# master_taylor2.net
KiCad netlist of a schematic drawn in EAGLE
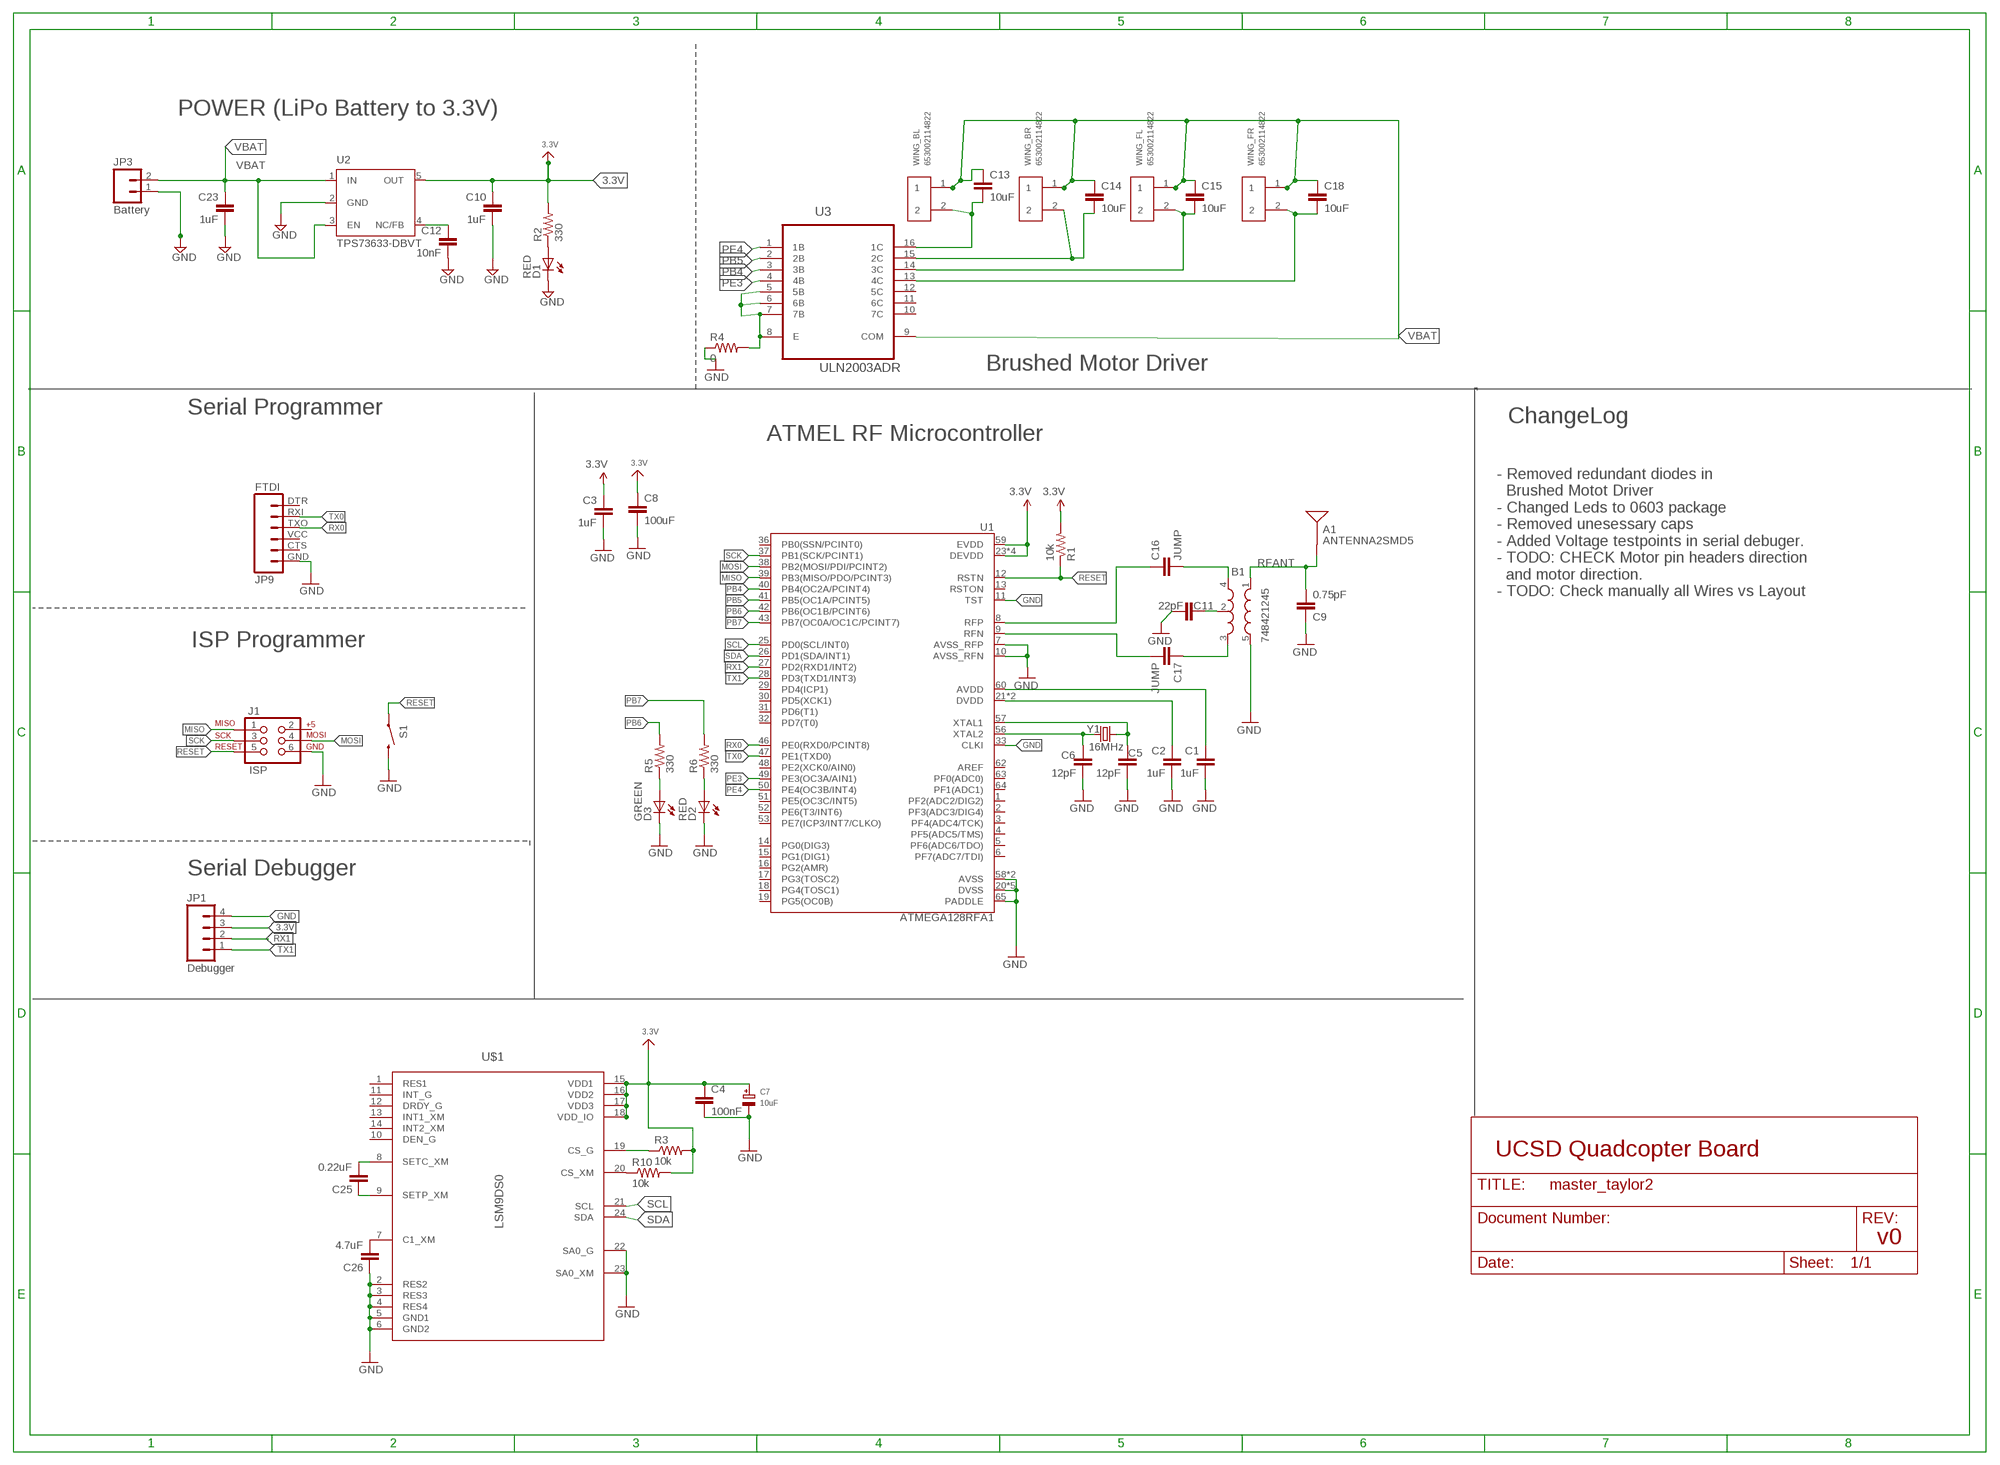
[diagram p0: schematic, sheet 1]

(export (version "E")
  (design (tool "Eeschema 10.0.6"))
  (components
    (comp (ref "A1")
      (value "ANTENNA2SMD5")
      (footprint "eagle-import:ANTENNA-CHIP5")
      (libsource (lib "eagle-import") (part "ANTENNA2SMD5"))
    )
    (comp (ref "B1")
      (value "748421245")
      (footprint "eagle-import:BALUN")
      (libsource (lib "eagle-import") (part "BALUN0805"))
    )
    (comp (ref "C1")
      (value "1uF")
      (footprint "eagle-import:0603-CAP")
      (libsource (lib "eagle-import") (part "CAP0603-CAP"))
    )
    (comp (ref "C2")
      (value "1uF")
      (footprint "eagle-import:0603-CAP")
      (libsource (lib "eagle-import") (part "CAP0603-CAP"))
    )
    (comp (ref "C3")
      (value "1uF")
      (footprint "eagle-import:0603-CAP")
      (libsource (lib "eagle-import") (part "CAP0603-CAP"))
    )
    (comp (ref "C4")
      (value "100nF")
      (footprint "eagle-import:0603-CAP")
      (libsource (lib "eagle-import") (part "CAP0603-CAP"))
    )
    (comp (ref "C5")
      (value "12pF")
      (footprint "eagle-import:0603-CAP")
      (libsource (lib "eagle-import") (part "CAP0603-CAP"))
    )
    (comp (ref "C6")
      (value "12pF")
      (footprint "eagle-import:0603-CAP")
      (libsource (lib "eagle-import") (part "CAP0603-CAP"))
    )
    (comp (ref "C7")
      (value "10uF")
      (footprint "eagle-import:EIA3216-18_A-W")
      (libsource (lib "eagle-import") (part "CAP_TANTALUMA/3216_WAVE"))
    )
    (comp (ref "C8")
      (value "100uF")
      (footprint "eagle-import:1206")
      (libsource (lib "eagle-import") (part "CAP1206"))
    )
    (comp (ref "C9")
      (value "0.75pF")
      (footprint "eagle-import:0603-CAP")
      (libsource (lib "eagle-import") (part "CAP0603-CAP"))
    )
    (comp (ref "C10")
      (value "1uF")
      (footprint "eagle-import:0603-CAP")
      (libsource (lib "eagle-import") (part "CAP0603-CAP"))
    )
    (comp (ref "C11")
      (value "22pF")
      (footprint "eagle-import:0603-CAP")
      (libsource (lib "eagle-import") (part "CAP0603-CAP"))
    )
    (comp (ref "C12")
      (value "10nF")
      (footprint "eagle-import:0603-CAP")
      (libsource (lib "eagle-import") (part "CAP0603-CAP"))
    )
    (comp (ref "C13")
      (value "10uF")
      (footprint "eagle-import:0603-CAP")
      (libsource (lib "eagle-import") (part "CAP0603-CAP"))
    )
    (comp (ref "C14")
      (value "10uF")
      (footprint "eagle-import:0603-CAP")
      (libsource (lib "eagle-import") (part "CAP0603-CAP"))
    )
    (comp (ref "C15")
      (value "10uF")
      (footprint "eagle-import:0603-CAP")
      (libsource (lib "eagle-import") (part "CAP0603-CAP"))
    )
    (comp (ref "C16")
      (value "JUMP")
      (footprint "eagle-import:0603-CAP")
      (libsource (lib "eagle-import") (part "CAP0603-CAP"))
    )
    (comp (ref "C17")
      (value "JUMP")
      (footprint "eagle-import:0603-CAP")
      (libsource (lib "eagle-import") (part "CAP0603-CAP"))
    )
    (comp (ref "C18")
      (value "10uF")
      (footprint "eagle-import:0603-CAP")
      (libsource (lib "eagle-import") (part "CAP0603-CAP"))
    )
    (comp (ref "C23")
      (value "1uF")
      (footprint "eagle-import:0603-CAP")
      (libsource (lib "eagle-import") (part "CAP0603-CAP"))
    )
    (comp (ref "C25")
      (value "0.22uF")
      (footprint "eagle-import:0603-CAP")
      (libsource (lib "eagle-import") (part "CAP0603-CAP"))
    )
    (comp (ref "C26")
      (value "4.7uF")
      (footprint "eagle-import:0603-CAP")
      (libsource (lib "eagle-import") (part "CAP0603-CAP"))
    )
    (comp (ref "D1")
      (value "RED")
      (footprint "eagle-import:CHIPLED_0603")
      (libsource (lib "eagle-import") (part "LEDCHIPLED_0603"))
    )
    (comp (ref "D2")
      (value "RED")
      (footprint "eagle-import:CHIPLED_0603")
      (libsource (lib "eagle-import") (part "LEDCHIPLED_0603"))
    )
    (comp (ref "D3")
      (value "GREEN")
      (footprint "eagle-import:CHIPLED_0603")
      (libsource (lib "eagle-import") (part "LEDCHIPLED_0603"))
    )
    (comp (ref "J1")
      (value "ISP")
      (footprint "eagle-import:2X3-NS")
      (libsource (lib "eagle-import") (part "AVR_SPI_PRG_6NS"))
    )
    (comp (ref "JP1")
      (value "Debugger")
      (footprint "eagle-import:1X04")
      (libsource (lib "eagle-import") (part "M04PTH"))
    )
    (comp (ref "JP3")
      (value "Battery")
      (footprint "eagle-import:1X02")
      (libsource (lib "eagle-import") (part "M02PTH"))
    )
    (comp (ref "JP9")
      (value "FTDI")
      (footprint "eagle-import:FTDI_BASIC")
      (libsource (lib "eagle-import") (part "FTDI_BASICPTH"))
    )
    (comp (ref "R1")
      (value "10k")
      (footprint "eagle-import:0603-RES")
      (libsource (lib "eagle-import") (part "SparkFun-Resistors_RESISTOR0603-RES"))
    )
    (comp (ref "R2")
      (value "330")
      (footprint "eagle-import:0603-RES")
      (libsource (lib "eagle-import") (part "SparkFun-Resistors_RESISTOR0603-RES"))
    )
    (comp (ref "R3")
      (value "10k")
      (footprint "eagle-import:0805")
      (libsource (lib "eagle-import") (part "RESISTOR0805-RES"))
    )
    (comp (ref "R4")
      (value "0")
      (footprint "eagle-import:0805")
      (libsource (lib "eagle-import") (part "RESISTOR0805-RES"))
    )
    (comp (ref "R5")
      (value "330")
      (footprint "eagle-import:0603-RES")
      (libsource (lib "eagle-import") (part "SparkFun-Resistors_RESISTOR0603-RES"))
    )
    (comp (ref "R6")
      (value "330")
      (footprint "eagle-import:0603-RES")
      (libsource (lib "eagle-import") (part "SparkFun-Resistors_RESISTOR0603-RES"))
    )
    (comp (ref "R10")
      (value "10k")
      (footprint "eagle-import:0805")
      (libsource (lib "eagle-import") (part "RESISTOR0805-RES"))
    )
    (comp (ref "S1")
      (value "SWITCH-MOMENTARY-2SMD")
      (footprint "eagle-import:TACTILE_SWITCH_SMD")
      (libsource (lib "eagle-import") (part "SWITCH-MOMENTARY-2SMD"))
    )
    (comp (ref "U$1")
      (value "LSM9DS0")
      (footprint "eagle-import:LGA-24")
      (libsource (lib "eagle-import") (part "LSM9DS0"))
    )
    (comp (ref "U1")
      (value "ATMEGA128RFA1")
      (footprint "eagle-import:QFN-64")
      (libsource (lib "eagle-import") (part "ATMEGA128RFA1"))
    )
    (comp (ref "U2")
      (value "TPS73633-DBVT")
      (footprint "eagle-import:SOT23-DBV")
      (libsource (lib "eagle-import") (part "TPS73633-DBVT"))
    )
    (comp (ref "U3")
      (value "ULN2003ADR")
      (footprint "eagle-import:SOIC127P600X175-16N")
      (libsource (lib "eagle-import") (part "ULN2003ADR"))
    )
    (comp (ref "WING_BL")
      (value "653002114822")
      (footprint "eagle-import:653002114822")
      (libsource (lib "eagle-import") (part "653002114822"))
    )
    (comp (ref "WING_BR")
      (value "653002114822")
      (footprint "eagle-import:653002114822")
      (libsource (lib "eagle-import") (part "653002114822"))
    )
    (comp (ref "WING_FL")
      (value "653002114822")
      (footprint "eagle-import:653002114822")
      (libsource (lib "eagle-import") (part "653002114822"))
    )
    (comp (ref "WING_FR")
      (value "653002114822")
      (footprint "eagle-import:653002114822")
      (libsource (lib "eagle-import") (part "653002114822"))
    )
    (comp (ref "Y1")
      (value "16MHz")
      (footprint "eagle-import:CRYSTAL-SMD-5X3")
      (libsource (lib "eagle-import") (part "CRYSTAL5X3"))
    )
  )
  (nets
    (net (code "1") (name "/RFANT") (class "Default")
      (node (ref "A1") (pin "FEED") (pinfunction "SIGNAL_FEED") (pintype "bidirectional"))
      (node (ref "B1") (pin "1") (pinfunction "IN_1") (pintype "bidirectional"))
      (node (ref "C9") (pin "2") (pinfunction "2_2") (pintype "passive"))
    )
    (net (code "2") (name "3.3V") (class "Default")
      (node (ref "C10") (pin "1") (pinfunction "1_1") (pintype "passive"))
      (node (ref "C3") (pin "1") (pinfunction "1_1") (pintype "passive"))
      (node (ref "C4") (pin "1") (pinfunction "1_1") (pintype "passive"))
      (node (ref "C7") (pin "+") (pinfunction "+_+") (pintype "passive"))
      (node (ref "C8") (pin "1") (pinfunction "1_1") (pintype "passive"))
      (node (ref "JP1") (pin "3") (pinfunction "3_3") (pintype "passive"))
      (node (ref "R1") (pin "2") (pinfunction "2_2") (pintype "passive"))
      (node (ref "R10") (pin "2") (pinfunction "2_2") (pintype "passive"))
      (node (ref "R2") (pin "2") (pinfunction "2_2") (pintype "passive"))
      (node (ref "R3") (pin "2") (pinfunction "2_2") (pintype "passive"))
      (node (ref "U$1") (pin "15") (pinfunction "VDD1_15") (pintype "bidirectional"))
      (node (ref "U$1") (pin "16") (pinfunction "VDD2_16") (pintype "bidirectional"))
      (node (ref "U$1") (pin "17") (pinfunction "VDD3_17") (pintype "bidirectional"))
      (node (ref "U$1") (pin "18") (pinfunction "VDD_IO_18") (pintype "bidirectional"))
      (node (ref "U1") (pin "23") (pinfunction "DEVDD_23") (pintype "bidirectional"))
      (node (ref "U1") (pin "34") (pinfunction "DEVDD_34") (pintype "bidirectional"))
      (node (ref "U1") (pin "44") (pinfunction "DEVDD_44") (pintype "bidirectional"))
      (node (ref "U1") (pin "54") (pinfunction "DEVDD_54") (pintype "bidirectional"))
      (node (ref "U1") (pin "59") (pinfunction "EVDD_59") (pintype "bidirectional"))
      (node (ref "U2") (pin "5") (pinfunction "OUT_5") (pintype "passive"))
    )
    (net (code "3") (name "GND") (class "Default")
      (node (ref "B1") (pin "5") (pinfunction "GND_5") (pintype "bidirectional"))
      (node (ref "C1") (pin "2") (pinfunction "2_2") (pintype "passive"))
      (node (ref "C10") (pin "2") (pinfunction "2_2") (pintype "passive"))
      (node (ref "C11") (pin "2") (pinfunction "2_2") (pintype "passive"))
      (node (ref "C12") (pin "2") (pinfunction "2_2") (pintype "passive"))
      (node (ref "C2") (pin "2") (pinfunction "2_2") (pintype "passive"))
      (node (ref "C23") (pin "2") (pinfunction "2_2") (pintype "passive"))
      (node (ref "C26") (pin "1") (pinfunction "1_1") (pintype "passive"))
      (node (ref "C3") (pin "2") (pinfunction "2_2") (pintype "passive"))
      (node (ref "C4") (pin "2") (pinfunction "2_2") (pintype "passive"))
      (node (ref "C5") (pin "2") (pinfunction "2_2") (pintype "passive"))
      (node (ref "C6") (pin "2") (pinfunction "2_2") (pintype "passive"))
      (node (ref "C7") (pin "-") (pinfunction "-_-") (pintype "passive"))
      (node (ref "C8") (pin "2") (pinfunction "2_2") (pintype "passive"))
      (node (ref "C9") (pin "1") (pinfunction "1_1") (pintype "passive"))
      (node (ref "D1") (pin "C") (pinfunction "C_C") (pintype "passive"))
      (node (ref "D2") (pin "C") (pinfunction "C_C") (pintype "passive"))
      (node (ref "D3") (pin "C") (pinfunction "C_C") (pintype "passive"))
      (node (ref "J1") (pin "6") (pinfunction "6_6") (pintype "passive"))
      (node (ref "JP1") (pin "4") (pinfunction "4_4") (pintype "passive"))
      (node (ref "JP3") (pin "1") (pinfunction "1_1") (pintype "passive"))
      (node (ref "JP9") (pin "GND") (pinfunction "6_GND") (pintype "passive"))
      (node (ref "R4") (pin "1") (pinfunction "1_1") (pintype "passive"))
      (node (ref "S1") (pin "3") (pinfunction "2_3") (pintype "passive"))
      (node (ref "U$1") (pin "2") (pinfunction "RES2_2") (pintype "bidirectional"))
      (node (ref "U$1") (pin "22") (pinfunction "SA0_G_22") (pintype "bidirectional"))
      (node (ref "U$1") (pin "23") (pinfunction "SA0_XM_23") (pintype "bidirectional"))
      (node (ref "U$1") (pin "3") (pinfunction "RES3_3") (pintype "bidirectional"))
      (node (ref "U$1") (pin "4") (pinfunction "RES4_4") (pintype "bidirectional"))
      (node (ref "U$1") (pin "5") (pinfunction "GND1_5") (pintype "bidirectional"))
      (node (ref "U$1") (pin "6") (pinfunction "GND2_6") (pintype "bidirectional"))
      (node (ref "U1") (pin "10") (pinfunction "AVSS_RFN_10") (pintype "bidirectional"))
      (node (ref "U1") (pin "11") (pinfunction "TST_11") (pintype "bidirectional"))
      (node (ref "U1") (pin "20") (pinfunction "DVSS_20") (pintype "bidirectional"))
      (node (ref "U1") (pin "24") (pinfunction "DVSS_24") (pintype "bidirectional"))
      (node (ref "U1") (pin "33") (pinfunction "CLKI_33") (pintype "bidirectional"))
      (node (ref "U1") (pin "35") (pinfunction "DVSS_35") (pintype "bidirectional"))
      (node (ref "U1") (pin "45") (pinfunction "DVSS_45") (pintype "bidirectional"))
      (node (ref "U1") (pin "55") (pinfunction "DVSS_55") (pintype "bidirectional"))
      (node (ref "U1") (pin "58") (pinfunction "AVSS_58") (pintype "bidirectional"))
      (node (ref "U1") (pin "61") (pinfunction "AVSS_61") (pintype "bidirectional"))
      (node (ref "U1") (pin "65") (pinfunction "PADDLE_65") (pintype "bidirectional"))
      (node (ref "U1") (pin "7") (pinfunction "AVSS_RFP_7") (pintype "bidirectional"))
      (node (ref "U2") (pin "2") (pinfunction "GND_2") (pintype "input"))
    )
    (net (code "4") (name "MISO") (class "Default")
      (node (ref "J1") (pin "1") (pinfunction "1_1") (pintype "passive"))
      (node (ref "U1") (pin "39") (pinfunction "PB3(MISO/PDO/PCINT3)_39") (pintype "bidirectional"))
    )
    (net (code "5") (name "MOSI") (class "Default")
      (node (ref "J1") (pin "4") (pinfunction "4_4") (pintype "passive"))
      (node (ref "U1") (pin "38") (pinfunction "PB2(MOSI/PDI/PCINT2)_38") (pintype "bidirectional"))
    )
    (net (code "6") (name "Net-(B1-GND-Pad2)") (class "Default")
      (node (ref "B1") (pin "2") (pinfunction "GND_2") (pintype "bidirectional"))
      (node (ref "C11") (pin "1") (pinfunction "1_1") (pintype "passive"))
    )
    (net (code "7") (name "Net-(B1-OUT1)") (class "Default")
      (node (ref "B1") (pin "4") (pinfunction "OUT1_4") (pintype "bidirectional"))
      (node (ref "C16") (pin "2") (pinfunction "2_2") (pintype "passive"))
    )
    (net (code "8") (name "Net-(B1-OUT2)") (class "Default")
      (node (ref "B1") (pin "3") (pinfunction "OUT2_3") (pintype "bidirectional"))
      (node (ref "C17") (pin "1") (pinfunction "1_1") (pintype "passive"))
    )
    (net (code "9") (name "Net-(C2-Pad1)") (class "Default")
      (node (ref "C2") (pin "1") (pinfunction "1_1") (pintype "passive"))
      (node (ref "U1") (pin "21") (pinfunction "DVDD_21") (pintype "bidirectional"))
      (node (ref "U1") (pin "22") (pinfunction "DVDD_22") (pintype "bidirectional"))
    )
    (net (code "10") (name "Net-(D1-PadA)") (class "Default")
      (node (ref "D1") (pin "A") (pinfunction "A_A") (pintype "passive"))
      (node (ref "R2") (pin "1") (pinfunction "1_1") (pintype "passive"))
    )
    (net (code "11") (name "Net-(D2-PadA)") (class "Default")
      (node (ref "D2") (pin "A") (pinfunction "A_A") (pintype "passive"))
      (node (ref "R6") (pin "1") (pinfunction "1_1") (pintype "passive"))
    )
    (net (code "12") (name "Net-(D3-PadA)") (class "Default")
      (node (ref "D3") (pin "A") (pinfunction "A_A") (pintype "passive"))
      (node (ref "R5") (pin "1") (pinfunction "1_1") (pintype "passive"))
    )
    (net (code "13") (name "Net-(U$1-C1_XM)") (class "Default")
      (node (ref "C26") (pin "2") (pinfunction "2_2") (pintype "passive"))
      (node (ref "U$1") (pin "7") (pinfunction "C1_XM_7") (pintype "bidirectional"))
    )
    (net (code "14") (name "Net-(U$1-CS_G)") (class "Default")
      (node (ref "R3") (pin "1") (pinfunction "1_1") (pintype "passive"))
      (node (ref "U$1") (pin "19") (pinfunction "CS_G_19") (pintype "bidirectional"))
    )
    (net (code "15") (name "Net-(U$1-CS_XM)") (class "Default")
      (node (ref "R10") (pin "1") (pinfunction "1_1") (pintype "passive"))
      (node (ref "U$1") (pin "20") (pinfunction "CS_XM_20") (pintype "bidirectional"))
    )
    (net (code "16") (name "Net-(U$1-SETC_XM)") (class "Default")
      (node (ref "C25") (pin "2") (pinfunction "2_2") (pintype "passive"))
      (node (ref "U$1") (pin "8") (pinfunction "SETC_XM_8") (pintype "bidirectional"))
    )
    (net (code "17") (name "Net-(U$1-SETP_XM)") (class "Default")
      (node (ref "C25") (pin "1") (pinfunction "1_1") (pintype "passive"))
      (node (ref "U$1") (pin "9") (pinfunction "SETP_XM_9") (pintype "bidirectional"))
    )
    (net (code "18") (name "Net-(U1-AVDD)") (class "Default")
      (node (ref "C1") (pin "1") (pinfunction "1_1") (pintype "passive"))
      (node (ref "U1") (pin "60") (pinfunction "AVDD_60") (pintype "bidirectional"))
    )
    (net (code "19") (name "Net-(U1-RFN)") (class "Default")
      (node (ref "C17") (pin "2") (pinfunction "2_2") (pintype "passive"))
      (node (ref "U1") (pin "9") (pinfunction "RFN_9") (pintype "bidirectional"))
    )
    (net (code "20") (name "Net-(U1-RFP)") (class "Default")
      (node (ref "C16") (pin "1") (pinfunction "1_1") (pintype "passive"))
      (node (ref "U1") (pin "8") (pinfunction "RFP_8") (pintype "bidirectional"))
    )
    (net (code "21") (name "Net-(U1-XTAL1)") (class "Default")
      (node (ref "C5") (pin "1") (pinfunction "1_1") (pintype "passive"))
      (node (ref "U1") (pin "57") (pinfunction "XTAL1_57") (pintype "bidirectional"))
      (node (ref "Y1") (pin "3") (pinfunction "2_3") (pintype "passive"))
    )
    (net (code "22") (name "Net-(U1-XTAL2)") (class "Default")
      (node (ref "C6") (pin "1") (pinfunction "1_1") (pintype "passive"))
      (node (ref "U1") (pin "56") (pinfunction "XTAL2_56") (pintype "bidirectional"))
      (node (ref "Y1") (pin "1") (pinfunction "1_1") (pintype "passive"))
    )
    (net (code "23") (name "Net-(U2-NC{slash}FB)") (class "Default")
      (node (ref "C12") (pin "1") (pinfunction "1_1") (pintype "passive"))
      (node (ref "U2") (pin "4") (pinfunction "NC/FB_4") (pintype "passive"))
    )
    (net (code "24") (name "Net-(U3-1C)") (class "Default")
      (node (ref "C13") (pin "2") (pinfunction "2_2") (pintype "passive"))
      (node (ref "U3") (pin "16") (pinfunction "1C_16") (pintype "output"))
      (node (ref "WING_BL") (pin "2") (pinfunction "2_2") (pintype "bidirectional"))
    )
    (net (code "25") (name "Net-(U3-2C)") (class "Default")
      (node (ref "C14") (pin "2") (pinfunction "2_2") (pintype "passive"))
      (node (ref "U3") (pin "15") (pinfunction "2C_15") (pintype "output"))
      (node (ref "WING_BR") (pin "2") (pinfunction "2_2") (pintype "bidirectional"))
    )
    (net (code "26") (name "Net-(U3-3C)") (class "Default")
      (node (ref "C15") (pin "2") (pinfunction "2_2") (pintype "passive"))
      (node (ref "U3") (pin "14") (pinfunction "3C_14") (pintype "output"))
      (node (ref "WING_FL") (pin "2") (pinfunction "2_2") (pintype "bidirectional"))
    )
    (net (code "27") (name "Net-(U3-4C)") (class "Default")
      (node (ref "C18") (pin "2") (pinfunction "2_2") (pintype "passive"))
      (node (ref "U3") (pin "13") (pinfunction "4C_13") (pintype "output"))
      (node (ref "WING_FR") (pin "2") (pinfunction "2_2") (pintype "bidirectional"))
    )
    (net (code "28") (name "Net-(U3-5B)") (class "Default")
      (node (ref "R4") (pin "2") (pinfunction "2_2") (pintype "passive"))
      (node (ref "U3") (pin "5") (pinfunction "5B_5") (pintype "input"))
      (node (ref "U3") (pin "6") (pinfunction "6B_6") (pintype "input"))
      (node (ref "U3") (pin "7") (pinfunction "7B_7") (pintype "input"))
      (node (ref "U3") (pin "8") (pinfunction "E_8") (pintype "input"))
    )
    (net (code "29") (name "PB4") (class "Default")
      (node (ref "U1") (pin "40") (pinfunction "PB4(OC2A/PCINT4)_40") (pintype "bidirectional"))
      (node (ref "U3") (pin "3") (pinfunction "3B_3") (pintype "input"))
    )
    (net (code "30") (name "PB5") (class "Default")
      (node (ref "U1") (pin "41") (pinfunction "PB5(OC1A/PCINT5)_41") (pintype "bidirectional"))
      (node (ref "U3") (pin "2") (pinfunction "2B_2") (pintype "input"))
    )
    (net (code "31") (name "PB6") (class "Default")
      (node (ref "R5") (pin "2") (pinfunction "2_2") (pintype "passive"))
      (node (ref "U1") (pin "42") (pinfunction "PB6(OC1B/PCINT6)_42") (pintype "bidirectional"))
    )
    (net (code "32") (name "PB7") (class "Default")
      (node (ref "R6") (pin "2") (pinfunction "2_2") (pintype "passive"))
      (node (ref "U1") (pin "43") (pinfunction "PB7(OC0A/OC1C/PCINT7)_43") (pintype "bidirectional"))
    )
    (net (code "33") (name "PE3") (class "Default")
      (node (ref "U1") (pin "49") (pinfunction "PE3(OC3A/AIN1)_49") (pintype "bidirectional"))
      (node (ref "U3") (pin "4") (pinfunction "4B_4") (pintype "input"))
    )
    (net (code "34") (name "PE4") (class "Default")
      (node (ref "U1") (pin "50") (pinfunction "PE4(OC3B/INT4)_50") (pintype "bidirectional"))
      (node (ref "U3") (pin "1") (pinfunction "1B_1") (pintype "input"))
    )
    (net (code "35") (name "RESET") (class "Default")
      (node (ref "J1") (pin "5") (pinfunction "5_5") (pintype "passive"))
      (node (ref "R1") (pin "1") (pinfunction "1_1") (pintype "passive"))
      (node (ref "S1") (pin "1") (pinfunction "1_1") (pintype "passive"))
      (node (ref "U1") (pin "12") (pinfunction "RSTN_12") (pintype "bidirectional"))
    )
    (net (code "36") (name "RX0") (class "Default")
      (node (ref "JP9") (pin "TXO") (pinfunction "3_TXO") (pintype "passive"))
      (node (ref "U1") (pin "46") (pinfunction "PE0(RXD0/PCINT8)_46") (pintype "bidirectional"))
    )
    (net (code "37") (name "RX1") (class "Default")
      (node (ref "JP1") (pin "2") (pinfunction "2_2") (pintype "passive"))
      (node (ref "U1") (pin "27") (pinfunction "PD2(RXD1/INT2)_27") (pintype "bidirectional"))
    )
    (net (code "38") (name "SCK") (class "Default")
      (node (ref "J1") (pin "3") (pinfunction "3_3") (pintype "passive"))
      (node (ref "U1") (pin "37") (pinfunction "PB1(SCK/PCINT1)_37") (pintype "bidirectional"))
    )
    (net (code "39") (name "SCL") (class "Default")
      (node (ref "U$1") (pin "21") (pinfunction "SCL_21") (pintype "bidirectional"))
      (node (ref "U1") (pin "25") (pinfunction "PD0(SCL/INT0)_25") (pintype "bidirectional"))
    )
    (net (code "40") (name "SDA") (class "Default")
      (node (ref "U$1") (pin "24") (pinfunction "SDA_24") (pintype "bidirectional"))
      (node (ref "U1") (pin "26") (pinfunction "PD1(SDA/INT1)_26") (pintype "bidirectional"))
    )
    (net (code "41") (name "TX0") (class "Default")
      (node (ref "JP9") (pin "RXI") (pinfunction "2_RXI") (pintype "passive"))
      (node (ref "U1") (pin "47") (pinfunction "PE1(TXD0)_47") (pintype "bidirectional"))
    )
    (net (code "42") (name "TX1") (class "Default")
      (node (ref "JP1") (pin "1") (pinfunction "1_1") (pintype "passive"))
      (node (ref "U1") (pin "28") (pinfunction "PD3(TXD1/INT3)_28") (pintype "bidirectional"))
    )
    (net (code "43") (name "VBAT") (class "Default")
      (node (ref "C13") (pin "1") (pinfunction "1_1") (pintype "passive"))
      (node (ref "C14") (pin "1") (pinfunction "1_1") (pintype "passive"))
      (node (ref "C15") (pin "1") (pinfunction "1_1") (pintype "passive"))
      (node (ref "C18") (pin "1") (pinfunction "1_1") (pintype "passive"))
      (node (ref "C23") (pin "1") (pinfunction "1_1") (pintype "passive"))
      (node (ref "JP3") (pin "2") (pinfunction "2_2") (pintype "passive"))
      (node (ref "U2") (pin "1") (pinfunction "IN_1") (pintype "input"))
      (node (ref "U2") (pin "3") (pinfunction "EN_3") (pintype "power_in"))
      (node (ref "U3") (pin "9") (pinfunction "COM_9") (pintype "output"))
      (node (ref "WING_BL") (pin "1") (pinfunction "1_1") (pintype "bidirectional"))
      (node (ref "WING_BR") (pin "1") (pinfunction "1_1") (pintype "bidirectional"))
      (node (ref "WING_FL") (pin "1") (pinfunction "1_1") (pintype "bidirectional"))
      (node (ref "WING_FR") (pin "1") (pinfunction "1_1") (pintype "bidirectional"))
    )
    (net (code "44") (name "unconnected-(J1-Pad2)") (class "Default")
      (node (ref "J1") (pin "2") (pinfunction "2_2") (pintype "passive"))
    )
    (net (code "45") (name "unconnected-(JP9-1-PadDTR)") (class "Default")
      (node (ref "JP9") (pin "DTR") (pinfunction "1_DTR") (pintype "passive"))
    )
    (net (code "46") (name "unconnected-(JP9-4-PadVCC)") (class "Default")
      (node (ref "JP9") (pin "VCC") (pinfunction "4_VCC") (pintype "passive"))
    )
    (net (code "47") (name "unconnected-(JP9-5-PadCTS)") (class "Default")
      (node (ref "JP9") (pin "CTS") (pinfunction "5_CTS") (pintype "passive"))
    )
    (net (code "48") (name "unconnected-(U$1-DEN_G-Pad10)") (class "Default")
      (node (ref "U$1") (pin "10") (pinfunction "DEN_G_10") (pintype "bidirectional"))
    )
    (net (code "49") (name "unconnected-(U$1-DRDY_G-Pad12)") (class "Default")
      (node (ref "U$1") (pin "12") (pinfunction "DRDY_G_12") (pintype "bidirectional"))
    )
    (net (code "50") (name "unconnected-(U$1-INT1_XM-Pad13)") (class "Default")
      (node (ref "U$1") (pin "13") (pinfunction "INT1_XM_13") (pintype "bidirectional"))
    )
    (net (code "51") (name "unconnected-(U$1-INT2_XM-Pad14)") (class "Default")
      (node (ref "U$1") (pin "14") (pinfunction "INT2_XM_14") (pintype "bidirectional"))
    )
    (net (code "52") (name "unconnected-(U$1-INT_G-Pad11)") (class "Default")
      (node (ref "U$1") (pin "11") (pinfunction "INT_G_11") (pintype "bidirectional"))
    )
    (net (code "53") (name "unconnected-(U$1-RES1-Pad1)") (class "Default")
      (node (ref "U$1") (pin "1") (pinfunction "RES1_1") (pintype "bidirectional"))
    )
    (net (code "54") (name "unconnected-(U1-AREF-Pad62)") (class "Default")
      (node (ref "U1") (pin "62") (pinfunction "AREF_62") (pintype "bidirectional"))
    )
    (net (code "55") (name "unconnected-(U1-PB0(SSN{slash}PCINT0)-Pad36)") (class "Default")
      (node (ref "U1") (pin "36") (pinfunction "PB0(SSN/PCINT0)_36") (pintype "bidirectional"))
    )
    (net (code "56") (name "unconnected-(U1-PD4(ICP1)-Pad29)") (class "Default")
      (node (ref "U1") (pin "29") (pinfunction "PD4(ICP1)_29") (pintype "bidirectional"))
    )
    (net (code "57") (name "unconnected-(U1-PD5(XCK1)-Pad30)") (class "Default")
      (node (ref "U1") (pin "30") (pinfunction "PD5(XCK1)_30") (pintype "bidirectional"))
    )
    (net (code "58") (name "unconnected-(U1-PD6(T1)-Pad31)") (class "Default")
      (node (ref "U1") (pin "31") (pinfunction "PD6(T1)_31") (pintype "bidirectional"))
    )
    (net (code "59") (name "unconnected-(U1-PD7(T0)-Pad32)") (class "Default")
      (node (ref "U1") (pin "32") (pinfunction "PD7(T0)_32") (pintype "bidirectional"))
    )
    (net (code "60") (name "unconnected-(U1-PE2(XCK0{slash}AIN0)-Pad48)") (class "Default")
      (node (ref "U1") (pin "48") (pinfunction "PE2(XCK0/AIN0)_48") (pintype "bidirectional"))
    )
    (net (code "61") (name "unconnected-(U1-PE5(OC3C{slash}INT5)-Pad51)") (class "Default")
      (node (ref "U1") (pin "51") (pinfunction "PE5(OC3C/INT5)_51") (pintype "bidirectional"))
    )
    (net (code "62") (name "unconnected-(U1-PE6(T3{slash}INT6)-Pad52)") (class "Default")
      (node (ref "U1") (pin "52") (pinfunction "PE6(T3/INT6)_52") (pintype "bidirectional"))
    )
    (net (code "63") (name "unconnected-(U1-PE7(ICP3{slash}INT7{slash}CLKO)-Pad53)") (class "Default")
      (node (ref "U1") (pin "53") (pinfunction "PE7(ICP3/INT7/CLKO)_53") (pintype "bidirectional"))
    )
    (net (code "64") (name "unconnected-(U1-PF0(ADC0)-Pad63)") (class "Default")
      (node (ref "U1") (pin "63") (pinfunction "PF0(ADC0)_63") (pintype "bidirectional"))
    )
    (net (code "65") (name "unconnected-(U1-PF1(ADC1)-Pad64)") (class "Default")
      (node (ref "U1") (pin "64") (pinfunction "PF1(ADC1)_64") (pintype "bidirectional"))
    )
    (net (code "66") (name "unconnected-(U1-PF2(ADC2{slash}DIG2)-Pad1)") (class "Default")
      (node (ref "U1") (pin "1") (pinfunction "PF2(ADC2/DIG2)_1") (pintype "bidirectional"))
    )
    (net (code "67") (name "unconnected-(U1-PF3(ADC3{slash}DIG4)-Pad2)") (class "Default")
      (node (ref "U1") (pin "2") (pinfunction "PF3(ADC3/DIG4)_2") (pintype "bidirectional"))
    )
    (net (code "68") (name "unconnected-(U1-PF4(ADC4{slash}TCK)-Pad3)") (class "Default")
      (node (ref "U1") (pin "3") (pinfunction "PF4(ADC4/TCK)_3") (pintype "bidirectional"))
    )
    (net (code "69") (name "unconnected-(U1-PF5(ADC5{slash}TMS)-Pad4)") (class "Default")
      (node (ref "U1") (pin "4") (pinfunction "PF5(ADC5/TMS)_4") (pintype "bidirectional"))
    )
    (net (code "70") (name "unconnected-(U1-PF6(ADC6{slash}TDO)-Pad5)") (class "Default")
      (node (ref "U1") (pin "5") (pinfunction "PF6(ADC6/TDO)_5") (pintype "bidirectional"))
    )
    (net (code "71") (name "unconnected-(U1-PF7(ADC7{slash}TDI)-Pad6)") (class "Default")
      (node (ref "U1") (pin "6") (pinfunction "PF7(ADC7/TDI)_6") (pintype "bidirectional"))
    )
    (net (code "72") (name "unconnected-(U1-PG0(DIG3)-Pad14)") (class "Default")
      (node (ref "U1") (pin "14") (pinfunction "PG0(DIG3)_14") (pintype "bidirectional"))
    )
    (net (code "73") (name "unconnected-(U1-PG1(DIG1)-Pad15)") (class "Default")
      (node (ref "U1") (pin "15") (pinfunction "PG1(DIG1)_15") (pintype "bidirectional"))
    )
    (net (code "74") (name "unconnected-(U1-PG2(AMR)-Pad16)") (class "Default")
      (node (ref "U1") (pin "16") (pinfunction "PG2(AMR)_16") (pintype "bidirectional"))
    )
    (net (code "75") (name "unconnected-(U1-PG3(TOSC2)-Pad17)") (class "Default")
      (node (ref "U1") (pin "17") (pinfunction "PG3(TOSC2)_17") (pintype "bidirectional"))
    )
    (net (code "76") (name "unconnected-(U1-PG4(TOSC1)-Pad18)") (class "Default")
      (node (ref "U1") (pin "18") (pinfunction "PG4(TOSC1)_18") (pintype "bidirectional"))
    )
    (net (code "77") (name "unconnected-(U1-PG5(OC0B)-Pad19)") (class "Default")
      (node (ref "U1") (pin "19") (pinfunction "PG5(OC0B)_19") (pintype "bidirectional"))
    )
    (net (code "78") (name "unconnected-(U1-RSTON-Pad13)") (class "Default")
      (node (ref "U1") (pin "13") (pinfunction "RSTON_13") (pintype "bidirectional"))
    )
    (net (code "79") (name "unconnected-(U3-5C-Pad12)") (class "Default")
      (node (ref "U3") (pin "12") (pinfunction "5C_12") (pintype "output"))
    )
    (net (code "80") (name "unconnected-(U3-6C-Pad11)") (class "Default")
      (node (ref "U3") (pin "11") (pinfunction "6C_11") (pintype "output"))
    )
    (net (code "81") (name "unconnected-(U3-7C-Pad10)") (class "Default")
      (node (ref "U3") (pin "10") (pinfunction "7C_10") (pintype "output"))
    )
  )
)
